# STLINK_Breakout.net
KiCad netlist of a schematic drawn in Altium Designer
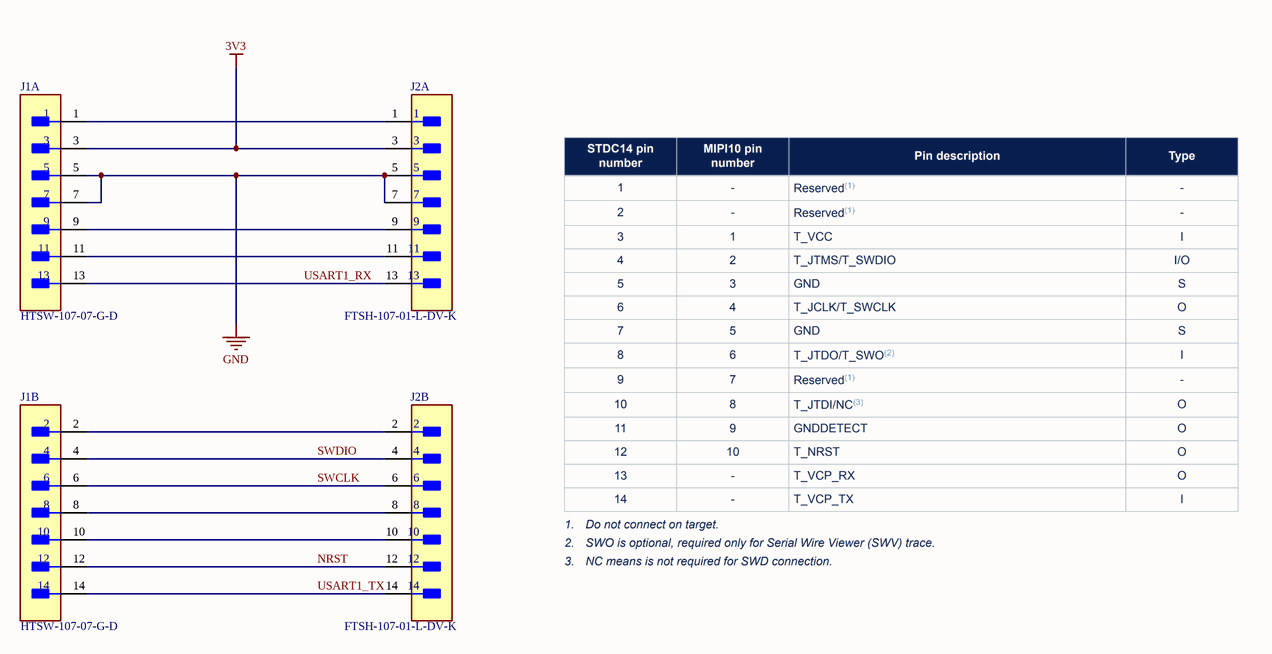
[diagram p0: STLINK_Breakout.SchDoc]

(export (version "E")
  (design (tool "Eeschema 10.0.6"))
  (components
    (comp (ref "J1")
      (value "HTSW-107-07-G-D")
      (footprint "FP-HTSW-107-07-G-D-MFG")
      (description "CONN HEADER VERT 14POS 2.54MM")
      (libsource (lib "") (part "7644e1a88aa4da17242a9b8d8257442_1"))
    )
    (comp (ref "J2")
      (value "FTSH-107-01-L-DV-K")
      (footprint "FP-FTSH-107-01-L-DV-K-MFG")
      (description "CONN HEADER SMD 14POS 1.27MM")
      (libsource (lib "Altium Content Vault") (part "7644e1a88aa4da17242a9b8d8257442"))
    )
  )
  (nets
    (net (code "1") (name "/NRST") (class "Default")
      (node (ref "J1") (pin "12") (pinfunction "12_12") (pintype "passive"))
      (node (ref "J2") (pin "12") (pinfunction "12_12") (pintype "passive"))
    )
    (net (code "2") (name "/SWCLK") (class "Default")
      (node (ref "J1") (pin "6") (pinfunction "6_6") (pintype "passive"))
      (node (ref "J2") (pin "6") (pinfunction "6_6") (pintype "passive"))
    )
    (net (code "3") (name "/SWDIO") (class "Default")
      (node (ref "J1") (pin "4") (pinfunction "4_4") (pintype "passive"))
      (node (ref "J2") (pin "4") (pinfunction "4_4") (pintype "passive"))
    )
    (net (code "4") (name "/USART1_RX") (class "Default")
      (node (ref "J1") (pin "13") (pinfunction "13_13") (pintype "passive"))
      (node (ref "J2") (pin "13") (pinfunction "13_13") (pintype "passive"))
    )
    (net (code "5") (name "/USART1_TX") (class "Default")
      (node (ref "J1") (pin "14") (pinfunction "14_14") (pintype "passive"))
      (node (ref "J2") (pin "14") (pinfunction "14_14") (pintype "passive"))
    )
    (net (code "6") (name "3V3") (class "Default")
      (node (ref "J1") (pin "3") (pinfunction "3_3") (pintype "passive"))
      (node (ref "J2") (pin "3") (pinfunction "3_3") (pintype "passive"))
    )
    (net (code "7") (name "GND") (class "Default")
      (node (ref "J1") (pin "5") (pinfunction "5_5") (pintype "passive"))
      (node (ref "J1") (pin "7") (pinfunction "7_7") (pintype "passive"))
      (node (ref "J2") (pin "5") (pinfunction "5_5") (pintype "passive"))
      (node (ref "J2") (pin "7") (pinfunction "7_7") (pintype "passive"))
    )
    (net (code "8") (name "Net-(J1-Pad1)") (class "Default")
      (node (ref "J1") (pin "1") (pinfunction "1_1") (pintype "passive"))
      (node (ref "J2") (pin "1") (pinfunction "1_1") (pintype "passive"))
    )
    (net (code "9") (name "Net-(J1-Pad2)") (class "Default")
      (node (ref "J1") (pin "2") (pinfunction "2_2") (pintype "passive"))
      (node (ref "J2") (pin "2") (pinfunction "2_2") (pintype "passive"))
    )
    (net (code "10") (name "Net-(J1-Pad8)") (class "Default")
      (node (ref "J1") (pin "8") (pinfunction "8_8") (pintype "passive"))
      (node (ref "J2") (pin "8") (pinfunction "8_8") (pintype "passive"))
    )
    (net (code "11") (name "Net-(J1-Pad9)") (class "Default")
      (node (ref "J1") (pin "9") (pinfunction "9_9") (pintype "passive"))
      (node (ref "J2") (pin "9") (pinfunction "9_9") (pintype "passive"))
    )
    (net (code "12") (name "Net-(J1-Pad10)") (class "Default")
      (node (ref "J1") (pin "10") (pinfunction "10_10") (pintype "passive"))
      (node (ref "J2") (pin "10") (pinfunction "10_10") (pintype "passive"))
    )
    (net (code "13") (name "Net-(J1-Pad11)") (class "Default")
      (node (ref "J1") (pin "11") (pinfunction "11_11") (pintype "passive"))
      (node (ref "J2") (pin "11") (pinfunction "11_11") (pintype "passive"))
    )
  )
)
